# JTAG_SWD.net
KiCad netlist of a schematic drawn in Altium Designer
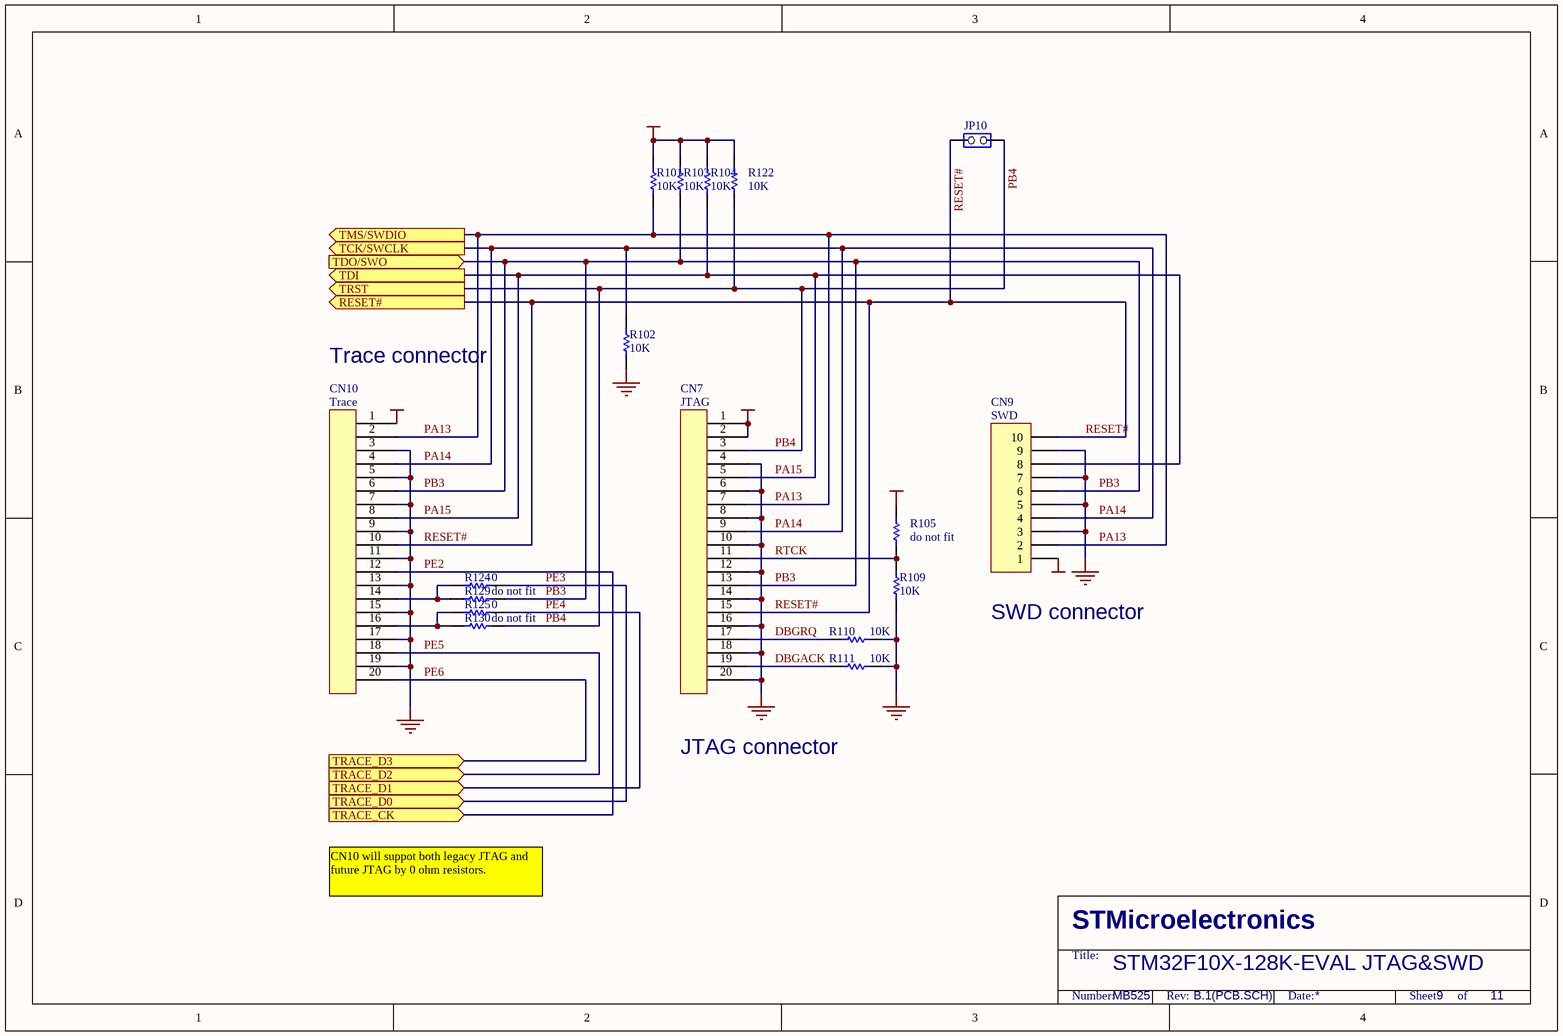
[diagram p0: JTAG&SWD.SchDoc]

(export (version "E")
  (design (tool "Eeschema 10.0.6"))
  (components
    (comp (ref "CN7") (value "JTAG") (footprint "IDC20S") (libsource (lib "*") (part "20PIN1")))
    (comp (ref "CN9")
      (value "SWD")
      (footprint "IDC10S")
      (description "Header, 10-Pin")
      (fields (field (name "PUBLISHER") "Altium Limited"))
      (libsource (lib "Miscellaneous Connectors") (part "Header 10"))
    )
    (comp (ref "CN10") (value "Trace") (footprint "IDC20S") (libsource (lib "*") (part "20PIN1")))
    (comp (ref "JP10") (value "~") (footprint "SIP2") (libsource (lib "*") (part "JP2")))
    (comp (ref "R101")
      (value "10K")
      (description "Resistor")
      (fields (field (name "PUBLISHER") "Altium Limited"))
      (libsource (lib "Miscellaneous Devices") (part "Res1"))
    )
    (comp (ref "R102")
      (value "10K")
      (description "Resistor")
      (fields (field (name "PUBLISHER") "Altium Limited"))
      (libsource (lib "Miscellaneous Devices") (part "Res1"))
    )
    (comp (ref "R103")
      (value "10K")
      (description "Resistor")
      (fields (field (name "PUBLISHER") "Altium Limited"))
      (libsource (lib "Miscellaneous Devices") (part "Res1"))
    )
    (comp (ref "R104")
      (value "10K")
      (description "Resistor")
      (fields (field (name "PUBLISHER") "Altium Limited"))
      (libsource (lib "Miscellaneous Devices") (part "Res1"))
    )
    (comp (ref "R105")
      (value "do not fit")
      (description "Resistor")
      (fields (field (name "PUBLISHER") "Altium Limited"))
      (libsource (lib "Miscellaneous Devices") (part "Res1"))
    )
    (comp (ref "R109")
      (value "10K")
      (description "Resistor")
      (fields (field (name "PUBLISHER") "Altium Limited"))
      (libsource (lib "Miscellaneous Devices") (part "Res1"))
    )
    (comp (ref "R110")
      (value "10K")
      (description "Resistor")
      (fields (field (name "PUBLISHER") "Altium Limited"))
      (libsource (lib "Miscellaneous Devices") (part "Res1"))
    )
    (comp (ref "R111")
      (value "10K")
      (description "Resistor")
      (fields (field (name "PUBLISHER") "Altium Limited"))
      (libsource (lib "Miscellaneous Devices") (part "Res1"))
    )
    (comp (ref "R122")
      (value "10K")
      (description "Resistor")
      (fields (field (name "PUBLISHER") "Altium Limited"))
      (libsource (lib "Miscellaneous Devices") (part "Res1"))
    )
    (comp (ref "R124")
      (value "0")
      (description "Resistor")
      (fields (field (name "PUBLISHER") "Altium Limited"))
      (libsource (lib "Miscellaneous Devices") (part "Res1"))
    )
    (comp (ref "R125")
      (value "0")
      (description "Resistor")
      (fields (field (name "PUBLISHER") "Altium Limited"))
      (libsource (lib "Miscellaneous Devices") (part "Res1"))
    )
    (comp (ref "R129")
      (value "do not fit")
      (description "Resistor")
      (fields (field (name "PUBLISHER") "Altium Limited"))
      (libsource (lib "Miscellaneous Devices") (part "Res1"))
    )
    (comp (ref "R130")
      (value "do not fit")
      (description "Resistor")
      (fields (field (name "PUBLISHER") "Altium Limited"))
      (libsource (lib "Miscellaneous Devices") (part "Res1"))
    )
  )
  (nets
    (net (code "1") (name "+3V3") (class "Default")
      (node (ref "CN10") (pin "1") (pintype "passive"))
      (node (ref "CN7") (pin "1") (pintype "passive"))
      (node (ref "CN7") (pin "2") (pintype "passive"))
      (node (ref "CN9") (pin "1") (pinfunction "1_1") (pintype "passive"))
      (node (ref "R101") (pin "2") (pinfunction "2_2") (pintype "passive"))
      (node (ref "R103") (pin "2") (pinfunction "2_2") (pintype "passive"))
      (node (ref "R104") (pin "2") (pinfunction "2_2") (pintype "passive"))
      (node (ref "R105") (pin "2") (pinfunction "2_2") (pintype "passive"))
      (node (ref "R122") (pin "2") (pinfunction "2_2") (pintype "passive"))
    )
    (net (code "2") (name "/DBGACK") (class "Default")
      (node (ref "CN7") (pin "19") (pintype "passive"))
      (node (ref "R111") (pin "1") (pinfunction "1_1") (pintype "passive"))
    )
    (net (code "3") (name "/DBGRQ") (class "Default")
      (node (ref "CN7") (pin "17") (pintype "passive"))
      (node (ref "R110") (pin "1") (pinfunction "1_1") (pintype "passive"))
    )
    (net (code "4") (name "/PA13") (class "Default")
      (node (ref "CN10") (pin "2") (pintype "passive"))
      (node (ref "CN7") (pin "7") (pintype "passive"))
      (node (ref "CN9") (pin "2") (pinfunction "2_2") (pintype "passive"))
      (node (ref "R101") (pin "1") (pinfunction "1_1") (pintype "passive"))
    )
    (net (code "5") (name "/PA14") (class "Default")
      (node (ref "CN10") (pin "4") (pintype "passive"))
      (node (ref "CN7") (pin "9") (pintype "passive"))
      (node (ref "CN9") (pin "4") (pinfunction "4_4") (pintype "passive"))
      (node (ref "R102") (pin "2") (pinfunction "2_2") (pintype "passive"))
    )
    (net (code "6") (name "/PA15") (class "Default")
      (node (ref "CN10") (pin "8") (pintype "passive"))
      (node (ref "CN7") (pin "5") (pintype "passive"))
      (node (ref "CN9") (pin "8") (pinfunction "8_8") (pintype "passive"))
      (node (ref "R104") (pin "1") (pinfunction "1_1") (pintype "passive"))
    )
    (net (code "7") (name "/PB3") (class "Default")
      (node (ref "CN10") (pin "6") (pintype "passive"))
      (node (ref "CN7") (pin "13") (pintype "passive"))
      (node (ref "CN9") (pin "6") (pinfunction "6_6") (pintype "passive"))
      (node (ref "R103") (pin "1") (pinfunction "1_1") (pintype "passive"))
      (node (ref "R129") (pin "2") (pinfunction "2_2") (pintype "passive"))
    )
    (net (code "8") (name "/PB4") (class "Default")
      (node (ref "CN7") (pin "3") (pintype "passive"))
      (node (ref "JP10") (pin "1") (pinfunction "COMMON_1") (pintype "passive"))
      (node (ref "R122") (pin "1") (pinfunction "1_1") (pintype "passive"))
      (node (ref "R130") (pin "2") (pinfunction "2_2") (pintype "passive"))
    )
    (net (code "9") (name "/PE2") (class "Default") (node (ref "CN10") (pin "12") (pintype "passive")))
    (net (code "10") (name "/PE3") (class "Default")
      (node (ref "R124") (pin "2") (pinfunction "2_2") (pintype "passive"))
    )
    (net (code "11") (name "/PE4") (class "Default")
      (node (ref "R125") (pin "2") (pinfunction "2_2") (pintype "passive"))
    )
    (net (code "12") (name "/PE5") (class "Default") (node (ref "CN10") (pin "18") (pintype "passive")))
    (net (code "13") (name "/PE6") (class "Default") (node (ref "CN10") (pin "20") (pintype "passive")))
    (net (code "14") (name "/RESET#") (class "Default")
      (node (ref "CN10") (pin "10") (pintype "passive"))
      (node (ref "CN7") (pin "15") (pintype "passive"))
      (node (ref "CN9") (pin "10") (pinfunction "10_10") (pintype "passive"))
      (node (ref "JP10") (pin "2") (pinfunction "NO_2") (pintype "passive"))
    )
    (net (code "15") (name "/RTCK") (class "Default")
      (node (ref "CN7") (pin "11") (pintype "passive"))
      (node (ref "R105") (pin "1") (pinfunction "1_1") (pintype "passive"))
      (node (ref "R109") (pin "2") (pinfunction "2_2") (pintype "passive"))
    )
    (net (code "16") (name "GND") (class "Default")
      (node (ref "CN10") (pin "11") (pintype "passive"))
      (node (ref "CN10") (pin "13") (pintype "passive"))
      (node (ref "CN10") (pin "15") (pintype "passive"))
      (node (ref "CN10") (pin "17") (pintype "passive"))
      (node (ref "CN10") (pin "19") (pintype "passive"))
      (node (ref "CN10") (pin "3") (pintype "passive"))
      (node (ref "CN10") (pin "5") (pintype "passive"))
      (node (ref "CN10") (pin "7") (pintype "passive"))
      (node (ref "CN10") (pin "9") (pintype "passive"))
      (node (ref "CN7") (pin "10") (pintype "passive"))
      (node (ref "CN7") (pin "12") (pintype "passive"))
      (node (ref "CN7") (pin "14") (pintype "passive"))
      (node (ref "CN7") (pin "16") (pintype "passive"))
      (node (ref "CN7") (pin "18") (pintype "passive"))
      (node (ref "CN7") (pin "20") (pintype "passive"))
      (node (ref "CN7") (pin "4") (pintype "passive"))
      (node (ref "CN7") (pin "6") (pintype "passive"))
      (node (ref "CN7") (pin "8") (pintype "passive"))
      (node (ref "CN9") (pin "3") (pinfunction "3_3") (pintype "passive"))
      (node (ref "CN9") (pin "5") (pinfunction "5_5") (pintype "passive"))
      (node (ref "CN9") (pin "7") (pinfunction "7_7") (pintype "passive"))
      (node (ref "CN9") (pin "9") (pinfunction "9_9") (pintype "passive"))
      (node (ref "R102") (pin "1") (pinfunction "1_1") (pintype "passive"))
      (node (ref "R109") (pin "1") (pinfunction "1_1") (pintype "passive"))
      (node (ref "R110") (pin "2") (pinfunction "2_2") (pintype "passive"))
      (node (ref "R111") (pin "2") (pinfunction "2_2") (pintype "passive"))
    )
    (net (code "17") (name "Net-(CN10-Pad14)") (class "Default")
      (node (ref "CN10") (pin "14") (pintype "passive"))
      (node (ref "R124") (pin "1") (pinfunction "1_1") (pintype "passive"))
      (node (ref "R129") (pin "1") (pinfunction "1_1") (pintype "passive"))
    )
    (net (code "18") (name "Net-(CN10-Pad16)") (class "Default")
      (node (ref "CN10") (pin "16") (pintype "passive"))
      (node (ref "R125") (pin "1") (pinfunction "1_1") (pintype "passive"))
      (node (ref "R130") (pin "1") (pinfunction "1_1") (pintype "passive"))
    )
  )
)
